# P02_Power_Management.net
KiCad netlist of a schematic drawn in Altium Designer
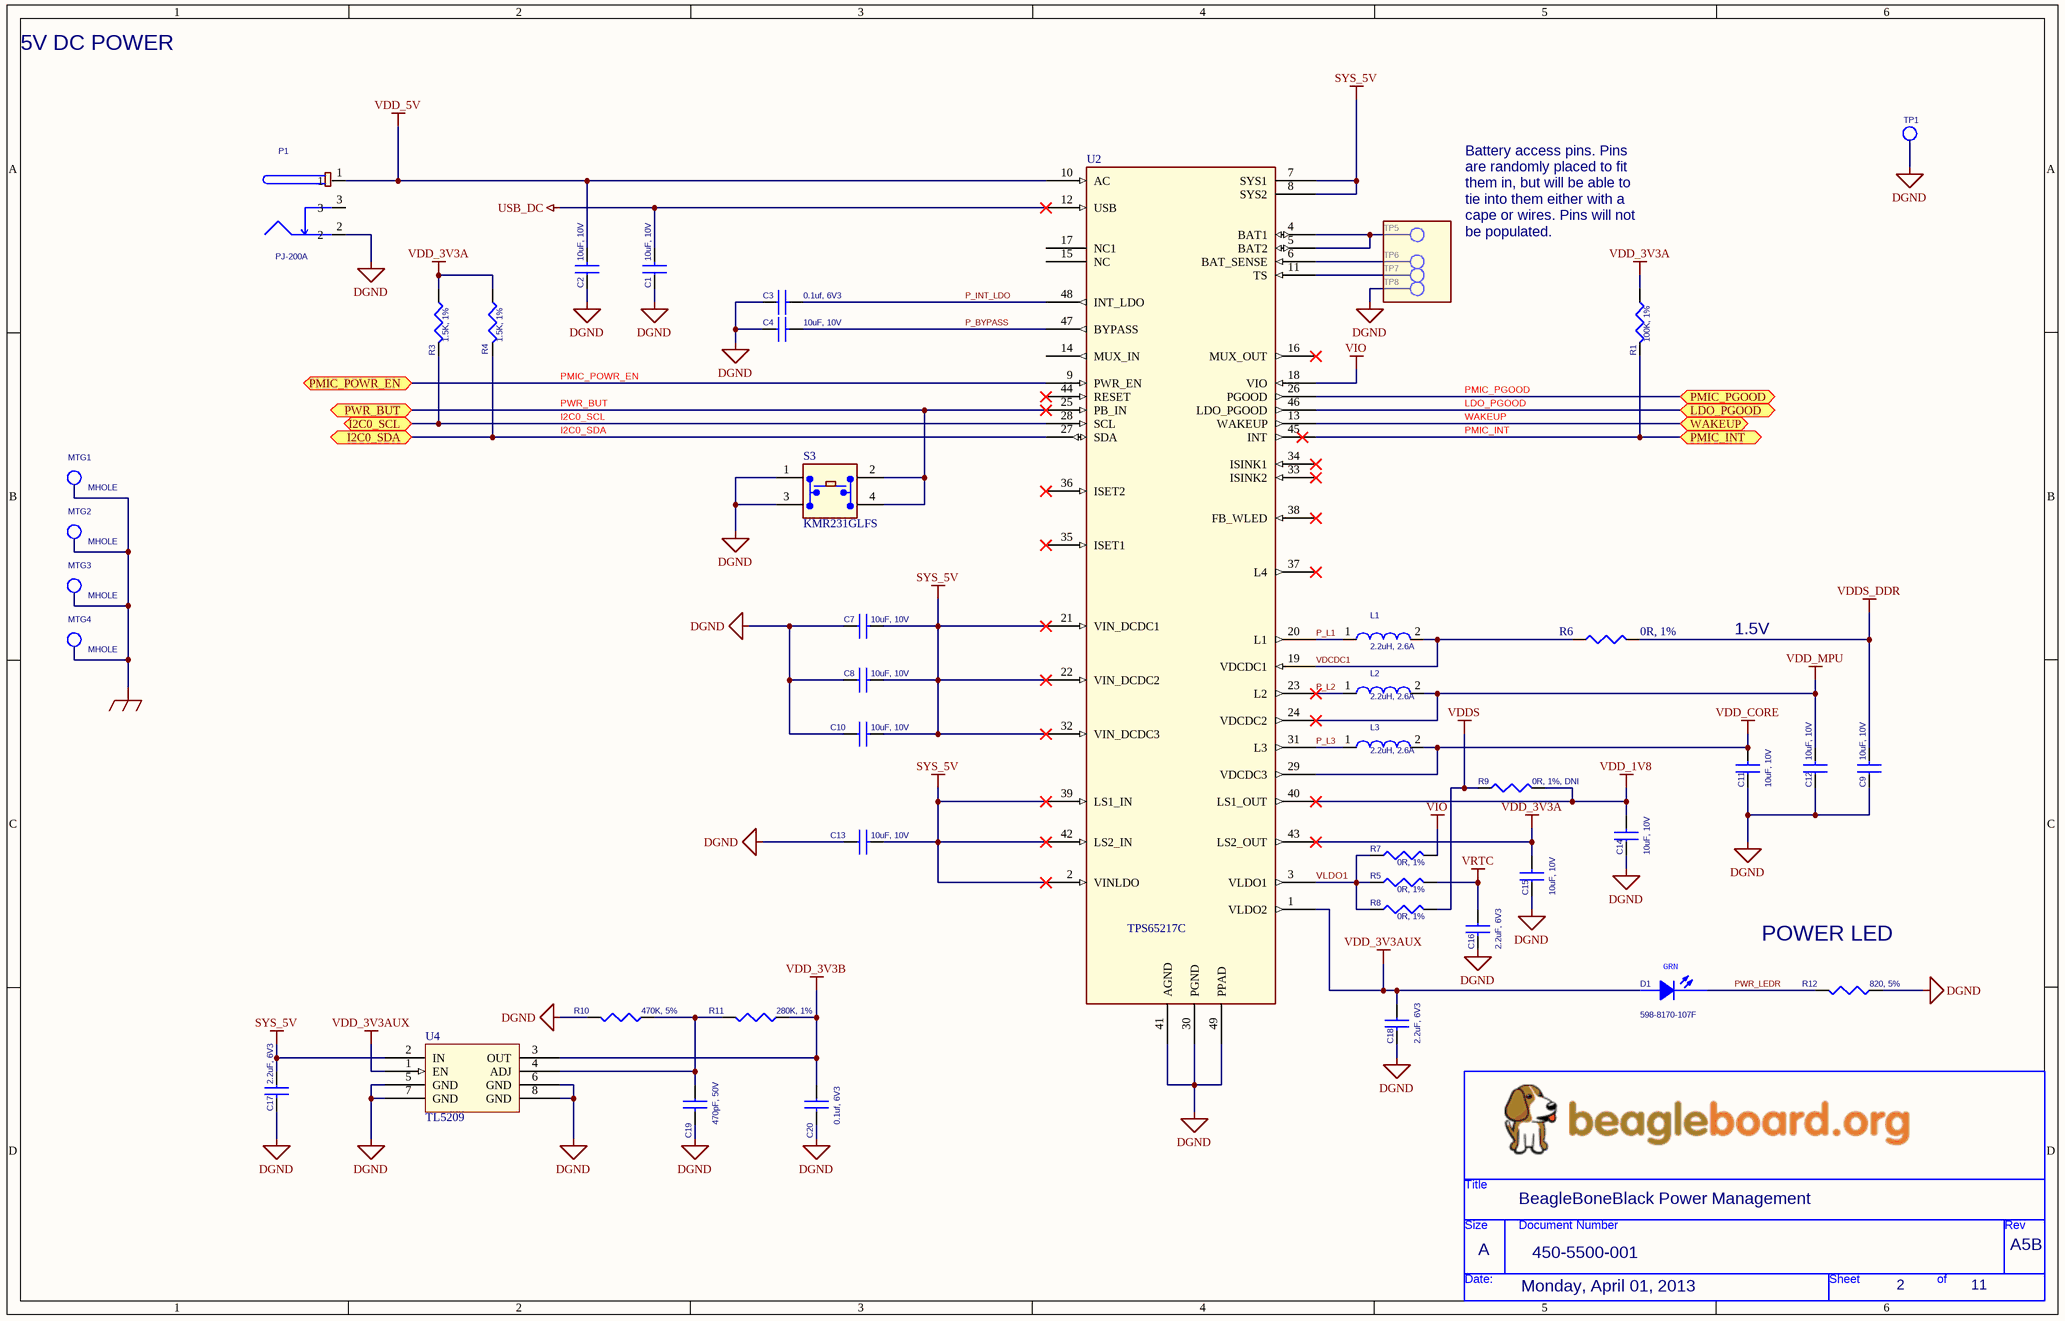
[diagram p0: P02_Power Management.SchDoc]

(export (version "E")
  (design (tool "Eeschema 10.0.6"))
  (components
    (comp (ref "C1")
      (value "10uF, 10V")
      (description "CAP CER 10UF 10V Y5V 0805")
      (fields
        (field (name "MANUFACTURER") "TDK Corporation")
        (field (name "MANUFACTURER PART NUMBER") "C2012Y5V1A106Z")
      )
      (libsource (lib "BEAGLEBONEBLACK_REV A5B") (part "CAP_4.7uF_X5R_6.3V_10%_0603"))
    )
    (comp (ref "C2")
      (value "10uF, 10V")
      (footprint "805")
      (description "CAP CER 10UF 10V Y5V 0805")
      (fields
        (field (name "MANUFACTURER") "TDK Corporation")
        (field (name "MANUFACTURER PART NUMBER") "C2012Y5V1A106Z")
      )
      (libsource (lib "BEAGLEBONEBLACK_REV A5B") (part "CAP_4.7uF_X5R_6.3V_10%_0603"))
    )
    (comp (ref "C3")
      (value "0.1uf, 6V3")
      (footprint "402")
      (description "CAP CER 0.1UF 6.3V 10% X5R 0402")
      (fields
        (field (name "MANUFACTURER") "TDK Corporation")
        (field (name "MANUFACTURER PART NUMBER") "C1005X5R0J104K050BA")
      )
      (libsource (lib "BEAGLEBONEBLACK_REV A5B") (part "CAP_10uF_Y5V_10V_10%_0805"))
    )
    (comp (ref "C4")
      (value "10uF, 10V")
      (description "CAP CER 10UF 10V Y5V 0805")
      (fields
        (field (name "MANUFACTURER") "TDK Corporation")
        (field (name "MANUFACTURER PART NUMBER") "C2012Y5V1A106Z")
      )
      (libsource (lib "BEAGLEBONEBLACK_REV A5B") (part "CAP_10uF_Y5V_10V_10%_0805"))
    )
    (comp (ref "C7")
      (value "10uF, 10V")
      (description "CAP CER 10UF 10V Y5V 0805")
      (fields
        (field (name "MANUFACTURER") "TDK Corporation")
        (field (name "MANUFACTURER PART NUMBER") "C2012Y5V1A106Z")
      )
      (libsource (lib "BEAGLEBONEBLACK_REV A5B") (part "CAP_10uF_Y5V_10V_10%_0805"))
    )
    (comp (ref "C8")
      (value "10uF, 10V")
      (description "CAP CER 10UF 10V Y5V 0805")
      (fields
        (field (name "MANUFACTURER") "TDK Corporation")
        (field (name "MANUFACTURER PART NUMBER") "C2012Y5V1A106Z")
      )
      (libsource (lib "BEAGLEBONEBLACK_REV A5B") (part "CAP_10uF_Y5V_10V_10%_0805"))
    )
    (comp (ref "C9")
      (value "10uF, 10V")
      (description "CAP CER 10UF 10V Y5V 0805")
      (fields
        (field (name "MANUFACTURER") "TDK Corporation")
        (field (name "MANUFACTURER PART NUMBER") "C2012Y5V1A106Z")
      )
      (libsource (lib "BEAGLEBONEBLACK_REV A5B") (part "CAP_10uF_Y5V_10V_10%_0805"))
    )
    (comp (ref "C10")
      (value "10uF, 10V")
      (description "CAP CER 10UF 10V Y5V 0805")
      (fields
        (field (name "MANUFACTURER") "TDK Corporation")
        (field (name "MANUFACTURER PART NUMBER") "C2012Y5V1A106Z")
      )
      (libsource (lib "BEAGLEBONEBLACK_REV A5B") (part "CAP_10uF_Y5V_10V_10%_0805"))
    )
    (comp (ref "C11")
      (value "10uF, 10V")
      (description "CAP CER 10UF 10V Y5V 0805")
      (fields
        (field (name "MANUFACTURER") "TDK Corporation")
        (field (name "MANUFACTURER PART NUMBER") "C2012Y5V1A106Z")
      )
      (libsource (lib "BEAGLEBONEBLACK_REV A5B") (part "CAP_10uF_Y5V_10V_10%_0805"))
    )
    (comp (ref "C12")
      (value "10uF, 10V")
      (description "CAP CER 10UF 10V Y5V 0805")
      (fields
        (field (name "MANUFACTURER") "TDK Corporation")
        (field (name "MANUFACTURER PART NUMBER") "C2012Y5V1A106Z")
      )
      (libsource (lib "BEAGLEBONEBLACK_REV A5B") (part "CAP_10uF_Y5V_10V_10%_0805"))
    )
    (comp (ref "C13")
      (value "10uF, 10V")
      (description "CAP CER 10UF 10V Y5V 0805")
      (fields
        (field (name "MANUFACTURER") "TDK Corporation")
        (field (name "MANUFACTURER PART NUMBER") "C2012Y5V1A106Z")
      )
      (libsource (lib "BEAGLEBONEBLACK_REV A5B") (part "CAP_10uF_Y5V_10V_10%_0805"))
    )
    (comp (ref "C14")
      (value "10uF, 10V")
      (description "CAP CER 10UF 10V Y5V 0805")
      (fields
        (field (name "MANUFACTURER") "TDK Corporation")
        (field (name "MANUFACTURER PART NUMBER") "C2012Y5V1A106Z")
      )
      (libsource (lib "BEAGLEBONEBLACK_REV A5B") (part "CAP_10uF_Y5V_10V_10%_0805"))
    )
    (comp (ref "C15")
      (value "10uF, 10V")
      (description "CAP CER 10UF 10V Y5V 0805")
      (fields
        (field (name "MANUFACTURER") "TDK Corporation")
        (field (name "MANUFACTURER PART NUMBER") "C2012Y5V1A106Z")
      )
      (libsource (lib "BEAGLEBONEBLACK_REV A5B") (part "CAP_10uF_Y5V_10V_10%_0805"))
    )
    (comp (ref "C16")
      (value "2.2uF, 6V3")
      (footprint "402")
      (description "CAP CER 2.2UF 6.3V 10% X5R 0402")
      (fields
        (field (name "MANUFACTURER") "TDK Corporation")
        (field (name "MANUFACTURER PART NUMBER") "C1005X5R0J225K050BC")
      )
      (libsource (lib "BEAGLEBONEBLACK_REV A5B") (part "CAP_2.2uF_X5R_6.3V_10%_0402"))
    )
    (comp (ref "C17")
      (value "2.2uF, 6V3")
      (footprint "402")
      (description "CAP CER 2.2UF 6.3V 10% X5R 0402")
      (fields
        (field (name "MANUFACTURER") "TDK Corporation")
        (field (name "MANUFACTURER PART NUMBER") "C1005X5R0J225K050BC")
      )
      (libsource (lib "BEAGLEBONEBLACK_REV A5B") (part "CAP_2.2uF_X5R_6.3V_10%_0402"))
    )
    (comp (ref "C18")
      (value "2.2uF, 6V3")
      (footprint "402")
      (description "CAP CER 2.2UF 6.3V 10% X5R 0402")
      (fields
        (field (name "MANUFACTURER") "TDK Corporation")
        (field (name "MANUFACTURER PART NUMBER") "C1005X5R0J225K050BC")
      )
      (libsource (lib "BEAGLEBONEBLACK_REV A5B") (part "CAP_2.2uF_X5R_6.3V_10%_0402"))
    )
    (comp (ref "C19")
      (value "470pF, 50V")
      (footprint "402")
      (description "CAP CER 470PF 50V 10% X7R 0402")
      (fields
        (field (name "MANUFACTURER") "Murata Electronics North America")
        (field (name "MANUFACTURER PART NUMBER") "GRM155R71H471KA01D")
      )
      (libsource (lib "BEAGLEBONEBLACK_REV A5B") (part "CAP_2.2uF_X5R_6.3V_10%_0402"))
    )
    (comp (ref "C20")
      (value "0.1uf, 6V3")
      (footprint "402")
      (description "CAP CER 0.1UF 6.3V 10% X5R 0402")
      (fields
        (field (name "MANUFACTURER") "TDK Corporation")
        (field (name "MANUFACTURER PART NUMBER") "C1005X5R0J104K050BA")
      )
      (libsource (lib "BEAGLEBONEBLACK_REV A5B") (part "CAP_0.1uF_X7R_16V_10% 0402"))
    )
    (comp (ref "D1")
      (value "598-8170-107F")
      (footprint "LED_0603")
      (description "LED GREEN CLEAR 0805 SMD")
      (fields
        (field (name "MANUFACTURER") "Lite-On Inc")
        (field (name "MANUFACTURER PART NUMBER") "LTST-C170KGKT")
      )
      (libsource (lib "BEAGLEBONEBLACK_REV A5B") (part "LED_LTST-C150GKT"))
    )
    (comp (ref "L1")
      (value "2.2uH, 2.6A")
      (footprint "2520")
      (description "Inductor 2.2uH smt 2.6A, 58 milliohm")
      (fields
        (field (name "MANUFACTURER") "Murata Electronics North America")
        (field (name "MANUFACTURER PART NUMBER") "LQM2HPN2R2MG0L")
      )
      (libsource (lib "BEAGLEBONEBLACK_REV A5B") (part "IND_2.2uH_2.6A_10%_SMD"))
    )
    (comp (ref "L2")
      (value "2.2uH, 2.6A")
      (footprint "2520")
      (description "INDUCTOR 2.2UH 20% 1300MA 1008")
      (fields (field (name "MFR") "TDK") (field (name "TIINTPARTNUMBER") "1L0025"))
      (libsource (lib "BEAGLEBONEBLACK_REV A5B") (part "IND_2.2uH_2.6A_10%_SMD"))
    )
    (comp (ref "L3")
      (value "2.2uH, 2.6A")
      (footprint "2520")
      (description "INDUCTOR 2.2UH 20% 1300MA 1008")
      (fields (field (name "MFR") "TDK") (field (name "TIINTPARTNUMBER") "1L0025"))
      (libsource (lib "BEAGLEBONEBLACK_REV A5B") (part "IND_2.2uH_2.6A_10%_SMD"))
    )
    (comp (ref "MTG1")
      (value "MHOLE")
      (footprint "MTGH200C125D_PL")
      (libsource (lib "BEAGLEBONEBLACK_REV A5B") (part "MHOLE"))
    )
    (comp (ref "MTG2")
      (value "MHOLE")
      (footprint "MTGH200C125D_PL")
      (libsource (lib "BEAGLEBONEBLACK_REV A5B") (part "MHOLE"))
    )
    (comp (ref "MTG3")
      (value "MHOLE")
      (footprint "MTGH200C125D_PL")
      (libsource (lib "BEAGLEBONEBLACK_REV A5B") (part "MHOLE"))
    )
    (comp (ref "MTG4")
      (value "MHOLE")
      (footprint "MTGH200C125D_PL")
      (libsource (lib "BEAGLEBONEBLACK_REV A5B") (part "MHOLE"))
    )
    (comp (ref "P1")
      (value "PJ-200A")
      (description "CONN PWR JACK 2.1X5.5MM HIGH CUR")
      (fields (field (name "MANUFACTURER") "CUI Inc") (field (name "MANUFACTURER PART NUMBER") "PJ-002AH"))
      (libsource (lib "BEAGLEBONEBLACK_REV A5B") (part "Power_Jack"))
    )
    (comp (ref "R1")
      (value "100K, 1%")
      (footprint "402")
      (description "RES 100K OHM 1/16W 1% 0402 SMD")
      (fields
        (field (name "MANUFACTURER") "Stackpole Electronics Inc")
        (field (name "MANUFACTURER PART NUMBER") "RMCF0402FT100K")
      )
      (libsource (lib "BEAGLEBONEBLACK_REV A5B") (part "RES_100K_1/16W_1%_0402"))
    )
    (comp (ref "R3")
      (value "1.5K, 1%")
      (footprint "402")
      (description "RES 1.50K OHM 1/16W 1% 0402 SMD")
      (fields
        (field (name "MANUFACTURER") "Yageo")
        (field (name "MANUFACTURER PART NUMBER") "RC0402FR-071K5L")
      )
      (libsource (lib "BEAGLEBONEBLACK_REV A5B") (part "RES_1.5K_1/16W_5%_0402"))
    )
    (comp (ref "R4")
      (value "1.5K, 1%")
      (footprint "402")
      (description "RES 1.50K OHM 1/16W 1% 0402 SMD")
      (fields
        (field (name "MANUFACTURER") "Yageo")
        (field (name "MANUFACTURER PART NUMBER") "RC0402FR-071K5L")
      )
      (libsource (lib "BEAGLEBONEBLACK_REV A5B") (part "RES_1.5K_1/16W_5%_0402"))
    )
    (comp (ref "R5")
      (value "0R, 1%")
      (footprint "402")
      (description "RES 0.0 OHM 1/16W 0402 SMD")
      (fields
        (field (name "MANUFACTURER") "Yageo")
        (field (name "MANUFACTURER PART NUMBER") "RC0402JR-070RL")
      )
      (libsource (lib "BEAGLEBONEBLACK_REV A5B") (part "RES_0_1/16W_1%_0402"))
    )
    (comp (ref "R6")
      (value "0R, 1%")
      (footprint "402")
      (description "RES 0.0 OHM 1/16W 0402 SMD")
      (fields
        (field (name "MANUFACTURER") "Yageo")
        (field (name "MANUFACTURER PART NUMBER") "RC0402JR-070RL")
      )
      (libsource (lib "BEAGLEBONEBLACK_REV A5B") (part "RES_0_1/16W_1%_0402"))
    )
    (comp (ref "R7")
      (value "0R, 1%")
      (footprint "402")
      (description "RES 0.0 OHM 1/16W 0402 SMD")
      (fields
        (field (name "MANUFACTURER") "Yageo")
        (field (name "MANUFACTURER PART NUMBER") "RC0402JR-070RL")
      )
      (libsource (lib "BEAGLEBONEBLACK_REV A5B") (part "RES_0_1/16W_1%_0402"))
    )
    (comp (ref "R8")
      (value "0R, 1%")
      (footprint "402")
      (description "RES 0.0 OHM 1/16W 0402 SMD")
      (fields
        (field (name "MANUFACTURER") "Yageo")
        (field (name "MANUFACTURER PART NUMBER") "RC0402JR-070RL")
      )
      (libsource (lib "BEAGLEBONEBLACK_REV A5B") (part "RES_0_1/16W_1%_0402"))
    )
    (comp (ref "R9")
      (value "0R, 1%, DNI")
      (footprint "402")
      (description "RES 0.0 OHM 1/16W 0402 SMD")
      (fields
        (field (name "MANUFACTURER") "Yageo")
        (field (name "MANUFACTURER PART NUMBER") "RC0402JR-070RL")
      )
      (libsource (lib "BEAGLEBONEBLACK_REV A5B") (part "RES_0_1/16W_1%_0402"))
    )
    (comp (ref "R10")
      (value "470K, 5%")
      (footprint "402")
      (description "RES 470K OHM 1/16W 1% 0402 SMD")
      (fields
        (field (name "MANUFACTURER") "Yageo")
        (field (name "MANUFACTURER PART NUMBER") "RC0402FR-07470KL")
      )
      (libsource (lib "BEAGLEBONEBLACK_REV A5B") (part "RES_470_1/10W_5%_0402"))
    )
    (comp (ref "R11")
      (value "280K, 1%")
      (footprint "402")
      (description "RES 280K OHM 1/16W 1% 0402 SMD")
      (fields
        (field (name "MANUFACTURER") "Stackpole Electronics Inc")
        (field (name "MANUFACTURER PART NUMBER") "RMCF0402FT280K")
      )
      (libsource (lib "BEAGLEBONEBLACK_REV A5B") (part "RES_470_1/10W_5%_0402"))
    )
    (comp (ref "R12")
      (value "820, 5%")
      (footprint "402")
      (description "RES 820 OHM 1/10W 5% 0402 SMD")
      (fields
        (field (name "MANUFACTURER") "Yageo")
        (field (name "MANUFACTURER PART NUMBER") "RC0402JR-07820RL")
      )
      (libsource (lib "BEAGLEBONEBLACK_REV A5B") (part "RES_470_1/10W_5%_0402"))
    )
    (comp (ref "S3")
      (value "KMR231GLFS")
      (footprint "SW4SMD_63X161LS")
      (description "Microminiature Tact Switch for SMT")
      (fields (field (name "MANUFACTURER") "C&K Components"))
      (libsource (lib "BEAGLEBONEBLACK_REV A5B") (part "KMR2"))
    )
    (comp (ref "TP1")
      (value "TESTPT1")
      (footprint "tp1-8040")
      (libsource (lib "BEAGLEBONEBLACK_REV A5B") (part "TESTPT1"))
    )
    (comp (ref "TP5")
      (value "TESTPT1")
      (footprint "TP60C33D")
      (libsource (lib "BEAGLEBONEBLACK_REV A5B") (part "TESTPT1"))
    )
    (comp (ref "TP6")
      (value "TESTPT1")
      (footprint "TP60C33D")
      (libsource (lib "BEAGLEBONEBLACK_REV A5B") (part "TESTPT1"))
    )
    (comp (ref "TP7")
      (value "TESTPT1")
      (footprint "TP60C33D")
      (libsource (lib "BEAGLEBONEBLACK_REV A5B") (part "TESTPT1"))
    )
    (comp (ref "TP8")
      (value "TESTPT1")
      (footprint "TP60C33D")
      (libsource (lib "BEAGLEBONEBLACK_REV A5B") (part "TESTPT1"))
    )
    (comp (ref "U2")
      (value "TPS65217C")
      (footprint "U_48_RSL")
      (description "IC PMIC BATT PWR SYST 48VQFN")
      (fields
        (field (name "MANUFACTURER") "Texas Instruments")
        (field (name "MANUFACTURER PART NUMBER") "TPS65217CRSLR")
      )
      (libsource (lib "BEAGLEBONEBLACK_REV A5B") (part "PWR_TPS65217_2"))
    )
    (comp (ref "U4")
      (value "TL5209")
      (footprint "SO8-25X75")
      (description "IC LDO VOLT REG 500MA 8-SOIC")
      (fields
        (field (name "MANUFACTURER") "Texas Instruments")
        (field (name "MANUFACTURER PART NUMBER") "TL5209DR")
      )
      (libsource (lib "BEAGLEBONEBLACK_REV A5B") (part "TL5209"))
    )
  )
  (nets
    (net (code "1") (name "/I2C0_SCL") (class "Default")
      (node (ref "R3") (pin "2") (pinfunction "2_2") (pintype "passive"))
      (node (ref "U2") (pin "28") (pinfunction "SCL_28") (pintype "input"))
    )
    (net (code "2") (name "/I2C0_SDA") (class "Default")
      (node (ref "R4") (pin "2") (pinfunction "2_2") (pintype "passive"))
      (node (ref "U2") (pin "27") (pinfunction "SDA_27") (pintype "bidirectional"))
    )
    (net (code "3") (name "/LDO_PGOOD") (class "Default")
      (node (ref "U2") (pin "46") (pinfunction "LDO_PGOOD_46") (pintype "output"))
    )
    (net (code "4") (name "/PMIC_INT") (class "Default")
      (node (ref "R1") (pin "2") (pinfunction "2_2") (pintype "passive"))
      (node (ref "U2") (pin "45") (pinfunction "INT_45") (pintype "output"))
    )
    (net (code "5") (name "/PMIC_PGOOD") (class "Default")
      (node (ref "U2") (pin "26") (pinfunction "PGOOD_26") (pintype "output"))
    )
    (net (code "6") (name "/PMIC_POWR_EN") (class "Default")
      (node (ref "U2") (pin "9") (pinfunction "PWR_EN_9") (pintype "input"))
    )
    (net (code "7") (name "/PWR_BUT") (class "Default")
      (node (ref "S3") (pin "2") (pinfunction "A2_2") (pintype "passive"))
      (node (ref "S3") (pin "4") (pinfunction "4_4") (pintype "power_in"))
      (node (ref "U2") (pin "25") (pinfunction "PB_IN_25") (pintype "input"))
    )
    (net (code "8") (name "/PWR_LEDR") (class "Default")
      (node (ref "D1") (pin "1") (pinfunction "C_1") (pintype "passive"))
      (node (ref "R12") (pin "2") (pinfunction "2_2") (pintype "passive"))
    )
    (net (code "9") (name "/P_BYPASS") (class "Default")
      (node (ref "C4") (pin "2") (pinfunction "2_2") (pintype "passive"))
      (node (ref "U2") (pin "47") (pinfunction "BYPASS_47") (pintype "output"))
    )
    (net (code "10") (name "/P_INT_LDO") (class "Default")
      (node (ref "C3") (pin "2") (pinfunction "2_2") (pintype "passive"))
      (node (ref "U2") (pin "48") (pinfunction "INT_LDO_48") (pintype "output"))
    )
    (net (code "11") (name "/P_L1") (class "Default")
      (node (ref "L1") (pin "1") (pinfunction "1_1") (pintype "passive"))
      (node (ref "U2") (pin "20") (pinfunction "L1_20") (pintype "output"))
    )
    (net (code "12") (name "/P_L2") (class "Default")
      (node (ref "L2") (pin "1") (pinfunction "1_1") (pintype "passive"))
      (node (ref "U2") (pin "23") (pinfunction "L2_23") (pintype "output"))
    )
    (net (code "13") (name "/P_L3") (class "Default")
      (node (ref "L3") (pin "1") (pinfunction "1_1") (pintype "passive"))
      (node (ref "U2") (pin "31") (pinfunction "L3_31") (pintype "output"))
    )
    (net (code "14") (name "/VDCDC1") (class "Default")
      (node (ref "L1") (pin "2") (pinfunction "2_2") (pintype "passive"))
      (node (ref "R6") (pin "1") (pinfunction "1_1") (pintype "passive"))
      (node (ref "U2") (pin "19") (pinfunction "VDCDC1_19") (pintype "input"))
    )
    (net (code "15") (name "/VLDO1") (class "Default")
      (node (ref "R5") (pin "1") (pinfunction "1_1") (pintype "passive"))
      (node (ref "R7") (pin "1") (pinfunction "1_1") (pintype "passive"))
      (node (ref "R8") (pin "1") (pinfunction "1_1") (pintype "passive"))
      (node (ref "U2") (pin "3") (pinfunction "VLDO1_3") (pintype "output"))
    )
    (net (code "16") (name "/WAKEUP") (class "Default")
      (node (ref "U2") (pin "13") (pinfunction "WAKEUP_13") (pintype "output"))
    )
    (net (code "17") (name "DGND") (class "Default")
      (node (ref "C1") (pin "1") (pinfunction "1_1") (pintype "passive"))
      (node (ref "C10") (pin "1") (pinfunction "1_1") (pintype "passive"))
      (node (ref "C11") (pin "1") (pinfunction "1_1") (pintype "passive"))
      (node (ref "C12") (pin "1") (pinfunction "1_1") (pintype "passive"))
      (node (ref "C13") (pin "1") (pinfunction "1_1") (pintype "passive"))
      (node (ref "C14") (pin "1") (pinfunction "1_1") (pintype "passive"))
      (node (ref "C15") (pin "1") (pinfunction "1_1") (pintype "passive"))
      (node (ref "C16") (pin "2") (pinfunction "2_2") (pintype "passive"))
      (node (ref "C17") (pin "2") (pinfunction "2_2") (pintype "passive"))
      (node (ref "C18") (pin "2") (pinfunction "2_2") (pintype "passive"))
      (node (ref "C19") (pin "2") (pinfunction "2_2") (pintype "passive"))
      (node (ref "C2") (pin "1") (pinfunction "1_1") (pintype "passive"))
      (node (ref "C20") (pin "2") (pinfunction "2_2") (pintype "passive"))
      (node (ref "C3") (pin "1") (pinfunction "1_1") (pintype "passive"))
      (node (ref "C4") (pin "1") (pinfunction "1_1") (pintype "passive"))
      (node (ref "C7") (pin "1") (pinfunction "1_1") (pintype "passive"))
      (node (ref "C8") (pin "1") (pinfunction "1_1") (pintype "passive"))
      (node (ref "C9") (pin "1") (pinfunction "1_1") (pintype "passive"))
      (node (ref "P1") (pin "2") (pinfunction "2_2") (pintype "passive"))
      (node (ref "R10") (pin "2") (pinfunction "2_2") (pintype "passive"))
      (node (ref "R12") (pin "1") (pinfunction "1_1") (pintype "passive"))
      (node (ref "S3") (pin "1") (pinfunction "A1_1") (pintype "passive"))
      (node (ref "S3") (pin "3") (pinfunction "A3_3") (pintype "passive"))
      (node (ref "TP1") (pin "1") (pinfunction "TP_1") (pintype "passive"))
      (node (ref "TP8") (pin "1") (pinfunction "TP_1") (pintype "passive"))
      (node (ref "U2") (pin "30") (pinfunction "PGND_30") (pintype "power_in"))
      (node (ref "U2") (pin "41") (pinfunction "AGND_41") (pintype "power_in"))
      (node (ref "U2") (pin "49") (pinfunction "PPAD_49") (pintype "power_in"))
      (node (ref "U4") (pin "5") (pinfunction "GND_5") (pintype "power_in"))
      (node (ref "U4") (pin "6") (pinfunction "GND_6") (pintype "power_in"))
      (node (ref "U4") (pin "7") (pinfunction "GND_7") (pintype "power_in"))
      (node (ref "U4") (pin "8") (pinfunction "GND_8") (pintype "power_in"))
    )
    (net (code "18") (name "GND_EARTH") (class "Default")
      (node (ref "MTG1") (pin "1") (pinfunction "TP_1") (pintype "passive"))
      (node (ref "MTG2") (pin "1") (pinfunction "TP_1") (pintype "passive"))
      (node (ref "MTG3") (pin "1") (pinfunction "TP_1") (pintype "passive"))
      (node (ref "MTG4") (pin "1") (pinfunction "TP_1") (pintype "passive"))
    )
    (net (code "19") (name "Net-(TP5-TP)") (class "Default")
      (node (ref "TP5") (pin "1") (pinfunction "TP_1") (pintype "passive"))
      (node (ref "U2") (pin "4") (pinfunction "BAT1_4") (pintype "bidirectional"))
      (node (ref "U2") (pin "5") (pinfunction "BAT2_5") (pintype "bidirectional"))
    )
    (net (code "20") (name "Net-(TP6-TP)") (class "Default")
      (node (ref "TP6") (pin "1") (pinfunction "TP_1") (pintype "passive"))
      (node (ref "U2") (pin "6") (pinfunction "BAT_SENSE_6") (pintype "input"))
    )
    (net (code "21") (name "Net-(TP7-TP)") (class "Default")
      (node (ref "TP7") (pin "1") (pinfunction "TP_1") (pintype "passive"))
      (node (ref "U2") (pin "11") (pinfunction "TS_11") (pintype "input"))
    )
    (net (code "22") (name "Net-(U4-ADJ)") (class "Default")
      (node (ref "C19") (pin "1") (pinfunction "1_1") (pintype "passive"))
      (node (ref "R10") (pin "1") (pinfunction "1_1") (pintype "passive"))
      (node (ref "R11") (pin "2") (pinfunction "2_2") (pintype "passive"))
      (node (ref "U4") (pin "4") (pinfunction "ADJ_4") (pintype "passive"))
    )
    (net (code "23") (name "SYS_5V") (class "Default")
      (node (ref "C10") (pin "2") (pinfunction "2_2") (pintype "passive"))
      (node (ref "C13") (pin "2") (pinfunction "2_2") (pintype "passive"))
      (node (ref "C17") (pin "1") (pinfunction "1_1") (pintype "passive"))
      (node (ref "C7") (pin "2") (pinfunction "2_2") (pintype "passive"))
      (node (ref "C8") (pin "2") (pinfunction "2_2") (pintype "passive"))
      (node (ref "U2") (pin "2") (pinfunction "VINLDO_2") (pintype "input"))
      (node (ref "U2") (pin "21") (pinfunction "VIN_DCDC1_21") (pintype "input"))
      (node (ref "U2") (pin "22") (pinfunction "VIN_DCDC2_22") (pintype "input"))
      (node (ref "U2") (pin "32") (pinfunction "VIN_DCDC3_32") (pintype "input"))
      (node (ref "U2") (pin "39") (pinfunction "LS1_IN_39") (pintype "input"))
      (node (ref "U2") (pin "42") (pinfunction "LS2_IN_42") (pintype "input"))
      (node (ref "U2") (pin "7") (pinfunction "SYS1_7") (pintype "passive"))
      (node (ref "U2") (pin "8") (pinfunction "SYS2_8") (pintype "passive"))
      (node (ref "U4") (pin "2") (pinfunction "IN_2") (pintype "power_in"))
    )
    (net (code "24") (name "USB_DC") (class "Default")
      (node (ref "C1") (pin "2") (pinfunction "2_2") (pintype "passive"))
      (node (ref "U2") (pin "12") (pinfunction "USB_12") (pintype "input"))
    )
    (net (code "25") (name "VDDS") (class "Default")
      (node (ref "R8") (pin "2") (pinfunction "2_2") (pintype "passive"))
      (node (ref "R9") (pin "1") (pinfunction "1_1") (pintype "passive"))
    )
    (net (code "26") (name "VDDS_DDR") (class "Default")
      (node (ref "C9") (pin "2") (pinfunction "2_2") (pintype "passive"))
      (node (ref "R6") (pin "2") (pinfunction "2_2") (pintype "passive"))
    )
    (net (code "27") (name "VDD_1V8") (class "Default")
      (node (ref "C14") (pin "2") (pinfunction "2_2") (pintype "passive"))
      (node (ref "R9") (pin "2") (pinfunction "2_2") (pintype "passive"))
      (node (ref "U2") (pin "40") (pinfunction "LS1_OUT_40") (pintype "output"))
    )
    (net (code "28") (name "VDD_3V3A") (class "Default")
      (node (ref "C15") (pin "2") (pinfunction "2_2") (pintype "passive"))
      (node (ref "R1") (pin "1") (pinfunction "1_1") (pintype "passive"))
      (node (ref "R3") (pin "1") (pinfunction "1_1") (pintype "passive"))
      (node (ref "R4") (pin "1") (pinfunction "1_1") (pintype "passive"))
      (node (ref "U2") (pin "43") (pinfunction "LS2_OUT_43") (pintype "output"))
    )
    (net (code "29") (name "VDD_3V3AUX") (class "Default")
      (node (ref "C18") (pin "1") (pinfunction "1_1") (pintype "passive"))
      (node (ref "D1") (pin "2") (pinfunction "A_2") (pintype "passive"))
      (node (ref "U2") (pin "1") (pinfunction "VLDO2_1") (pintype "output"))
      (node (ref "U4") (pin "1") (pinfunction "EN_1") (pintype "input"))
    )
    (net (code "30") (name "VDD_3V3B") (class "Default")
      (node (ref "C20") (pin "1") (pinfunction "1_1") (pintype "passive"))
      (node (ref "R11") (pin "1") (pinfunction "1_1") (pintype "passive"))
      (node (ref "U4") (pin "3") (pinfunction "OUT_3") (pintype "power_in"))
    )
    (net (code "31") (name "VDD_5V") (class "Default")
      (node (ref "C2") (pin "2") (pinfunction "2_2") (pintype "passive"))
      (node (ref "P1") (pin "1") (pinfunction "1_1") (pintype "passive"))
      (node (ref "U2") (pin "10") (pinfunction "AC_10") (pintype "input"))
    )
    (net (code "32") (name "VDD_CORE") (class "Default")
      (node (ref "C11") (pin "2") (pinfunction "2_2") (pintype "passive"))
      (node (ref "L3") (pin "2") (pinfunction "2_2") (pintype "passive"))
      (node (ref "U2") (pin "29") (pinfunction "VDCDC3_29") (pintype "output"))
    )
    (net (code "33") (name "VDD_MPU") (class "Default")
      (node (ref "C12") (pin "2") (pinfunction "2_2") (pintype "passive"))
      (node (ref "L2") (pin "2") (pinfunction "2_2") (pintype "passive"))
      (node (ref "U2") (pin "24") (pinfunction "VDCDC2_24") (pintype "output"))
    )
    (net (code "34") (name "VIO") (class "Default")
      (node (ref "R7") (pin "2") (pinfunction "2_2") (pintype "passive"))
      (node (ref "U2") (pin "18") (pinfunction "VIO_18") (pintype "input"))
    )
    (net (code "35") (name "VRTC") (class "Default")
      (node (ref "C16") (pin "1") (pinfunction "1_1") (pintype "passive"))
      (node (ref "R5") (pin "2") (pinfunction "2_2") (pintype "passive"))
    )
    (net (code "36") (name "unconnected-(P1-Pad3)") (class "Default")
      (node (ref "P1") (pin "3") (pinfunction "3_3") (pintype "passive"))
    )
    (net (code "37") (name "unconnected-(U2-FB_WLED-Pad38)") (class "Default")
      (node (ref "U2") (pin "38") (pinfunction "FB_WLED_38") (pintype "input+no_connect"))
    )
    (net (code "38") (name "unconnected-(U2-ISET1-Pad35)") (class "Default")
      (node (ref "U2") (pin "35") (pinfunction "ISET1_35") (pintype "input+no_connect"))
    )
    (net (code "39") (name "unconnected-(U2-ISET2-Pad36)") (class "Default")
      (node (ref "U2") (pin "36") (pinfunction "ISET2_36") (pintype "input+no_connect"))
    )
    (net (code "40") (name "unconnected-(U2-ISINK1-Pad34)") (class "Default")
      (node (ref "U2") (pin "34") (pinfunction "ISINK1_34") (pintype "input+no_connect"))
    )
    (net (code "41") (name "unconnected-(U2-ISINK2-Pad33)") (class "Default")
      (node (ref "U2") (pin "33") (pinfunction "ISINK2_33") (pintype "input+no_connect"))
    )
    (net (code "42") (name "unconnected-(U2-L4-Pad37)") (class "Default")
      (node (ref "U2") (pin "37") (pinfunction "L4_37") (pintype "output+no_connect"))
    )
    (net (code "43") (name "unconnected-(U2-MUX_IN-Pad14)") (class "Default")
      (node (ref "U2") (pin "14") (pinfunction "MUX_IN_14") (pintype "output"))
    )
    (net (code "44") (name "unconnected-(U2-MUX_OUT-Pad16)") (class "Default")
      (node (ref "U2") (pin "16") (pinfunction "MUX_OUT_16") (pintype "output+no_connect"))
    )
    (net (code "45") (name "unconnected-(U2-NC-Pad15)") (class "Default")
      (node (ref "U2") (pin "15") (pinfunction "NC_15") (pintype "passive"))
    )
    (net (code "46") (name "unconnected-(U2-NC1-Pad17)") (class "Default")
      (node (ref "U2") (pin "17") (pinfunction "NC1_17") (pintype "passive"))
    )
    (net (code "47") (name "unconnected-(U2-RESET-Pad44)") (class "Default")
      (node (ref "U2") (pin "44") (pinfunction "RESET_44") (pintype "input+no_connect"))
    )
  )
)
